# MCU.net
KiCad netlist of a schematic drawn in Altium Designer
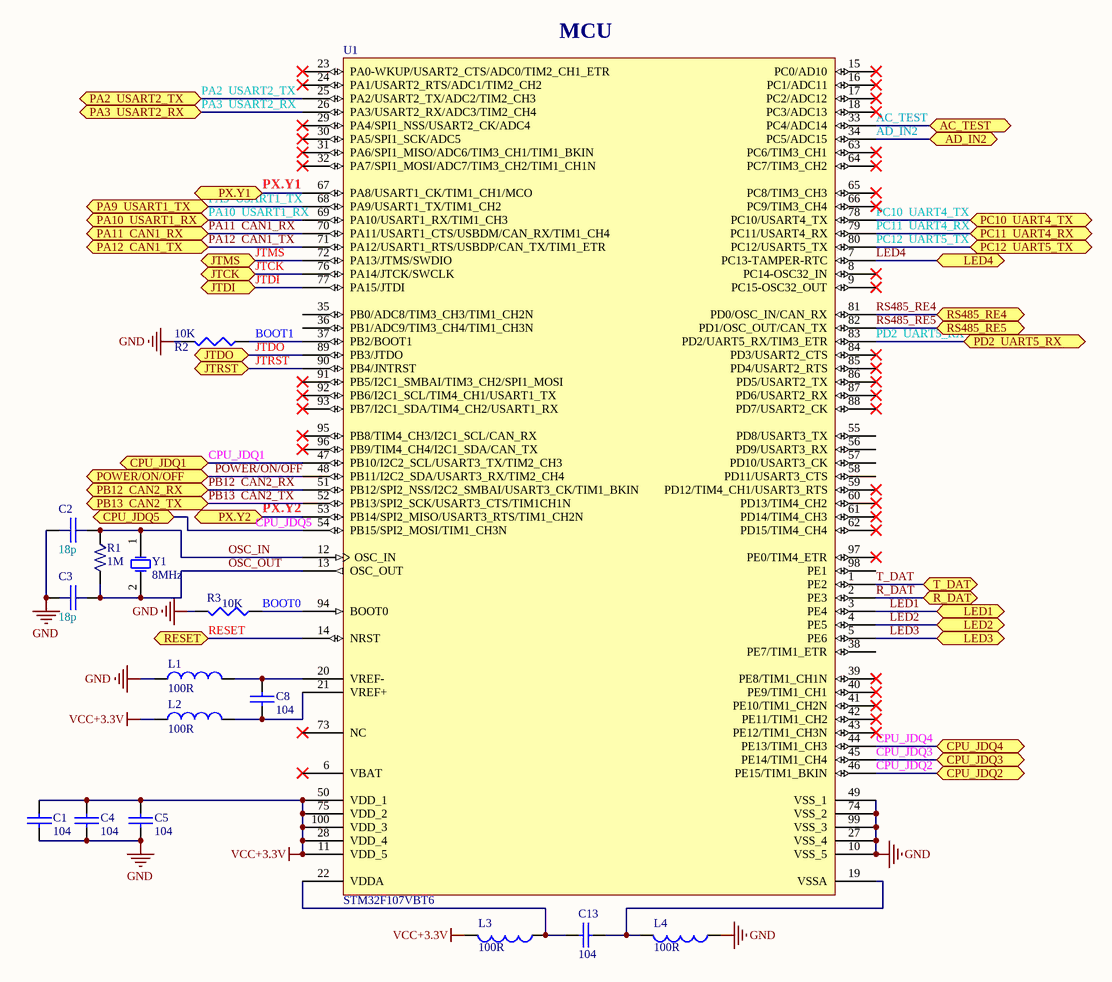
[diagram p0: MCU.SchDoc]

(export (version "E")
  (design (tool "Eeschema 10.0.6"))
  (components
    (comp (ref "C1") (value "104") (footprint "0603") (libsource (lib "INSPUR_SCH") (part "CAP")))
    (comp (ref "C2")
      (value "18p")
      (footprint "0603")
      (description "陶瓷电容")
      (libsource (lib "8CF_V6") (part "CAP"))
    )
    (comp (ref "C3")
      (value "18p")
      (footprint "0603")
      (description "陶瓷电容")
      (libsource (lib "8CF_V6") (part "CAP"))
    )
    (comp (ref "C4") (value "104") (footprint "0603") (libsource (lib "INSPUR_SCH") (part "CAP")))
    (comp (ref "C5") (value "104") (footprint "0603") (libsource (lib "INSPUR_SCH") (part "CAP")))
    (comp (ref "C8") (value "104") (footprint "0603") (libsource (lib "INSPUR_SCH") (part "CAP")))
    (comp (ref "C13") (value "104") (footprint "0603") (libsource (lib "INSPUR_SCH") (part "CAP")))
    (comp (ref "L1") (value "100R") (footprint "0805") (libsource (lib "INSPUR_SCH") (part "INDUCTOR")))
    (comp (ref "L2") (value "100R") (footprint "0805") (libsource (lib "INSPUR_SCH") (part "INDUCTOR")))
    (comp (ref "L3") (value "100R") (footprint "0805") (libsource (lib "INSPUR_SCH") (part "INDUCTOR")))
    (comp (ref "L4") (value "100R") (footprint "0805") (libsource (lib "INSPUR_SCH") (part "INDUCTOR")))
    (comp (ref "R1")
      (value "1M")
      (footprint "0805")
      (description "高精度电阻")
      (libsource (lib "8CF_V6") (part "RES-1%"))
    )
    (comp (ref "R2") (value "10K") (footprint "0603") (libsource (lib "INSPUR_SCH") (part "RES1")))
    (comp (ref "R3") (value "10K") (footprint "0603") (libsource (lib "INSPUR_SCH") (part "RES1")))
    (comp (ref "U1")
      (value "STM32F107VBT6")
      (footprint "LQFP100_L")
      (libsource (lib "mylib") (part "STM32F107VBT6"))
    )
    (comp (ref "Y1")
      (value "8MHz")
      (footprint "XTAL_US")
      (description "Crystal Oscillator")
      (fields (field (name "PUBLISHER") "Altium Limited"))
      (libsource (lib "mylib") (part "XTAL"))
    )
  )
  (nets
    (net (code "1") (name "/AC_TEST") (class "Default")
      (node (ref "U1") (pin "33") (pinfunction "PC4/ADC14_33") (pintype "bidirectional"))
    )
    (net (code "2") (name "/AD_IN2") (class "Default")
      (node (ref "U1") (pin "34") (pinfunction "PC5/ADC15_34") (pintype "bidirectional"))
    )
    (net (code "3") (name "/BOOT0") (class "Default")
      (node (ref "R3") (pin "1") (pinfunction "1_1") (pintype "passive"))
      (node (ref "U1") (pin "94") (pinfunction "BOOT0_94") (pintype "input"))
    )
    (net (code "4") (name "/BOOT1") (class "Default")
      (node (ref "R2") (pin "1") (pinfunction "1_1") (pintype "passive"))
      (node (ref "U1") (pin "37") (pinfunction "PB2/BOOT1_37") (pintype "bidirectional"))
    )
    (net (code "5") (name "/CPU_JDQ1") (class "Default")
      (node (ref "U1") (pin "47") (pinfunction "PB10/I2C2_SCL/USART3_TX/TIM2_CH3_47") (pintype "bidirectional"))
    )
    (net (code "6") (name "/CPU_JDQ2") (class "Default")
      (node (ref "U1") (pin "46") (pinfunction "PE15/TIM1_BKIN_46") (pintype "bidirectional"))
    )
    (net (code "7") (name "/CPU_JDQ3") (class "Default")
      (node (ref "U1") (pin "45") (pinfunction "PE14/TIM1_CH4_45") (pintype "bidirectional"))
    )
    (net (code "8") (name "/CPU_JDQ4") (class "Default")
      (node (ref "U1") (pin "44") (pinfunction "PE13/TIM1_CH3_44") (pintype "bidirectional"))
    )
    (net (code "9") (name "/CPU_JDQ5") (class "Default")
      (node (ref "U1") (pin "54") (pinfunction "PB15/SPI2_MOSI/TIM1_CH3N_54") (pintype "bidirectional"))
    )
    (net (code "10") (name "/JTCK") (class "Default")
      (node (ref "U1") (pin "76") (pinfunction "PA14/JTCK/SWCLK_76") (pintype "bidirectional"))
    )
    (net (code "11") (name "/JTDI") (class "Default")
      (node (ref "U1") (pin "77") (pinfunction "PA15/JTDI_77") (pintype "bidirectional"))
    )
    (net (code "12") (name "/JTDO") (class "Default")
      (node (ref "U1") (pin "89") (pinfunction "PB3/JTDO_89") (pintype "bidirectional"))
    )
    (net (code "13") (name "/JTMS") (class "Default")
      (node (ref "U1") (pin "72") (pinfunction "PA13/JTMS/SWDIO_72") (pintype "bidirectional"))
    )
    (net (code "14") (name "/JTRST") (class "Default")
      (node (ref "U1") (pin "90") (pinfunction "PB4/JNTRST_90") (pintype "bidirectional"))
    )
    (net (code "15") (name "/LED1") (class "Default")
      (node (ref "U1") (pin "3") (pinfunction "PE4_3") (pintype "bidirectional"))
    )
    (net (code "16") (name "/LED2") (class "Default")
      (node (ref "U1") (pin "4") (pinfunction "PE5_4") (pintype "bidirectional"))
    )
    (net (code "17") (name "/LED3") (class "Default")
      (node (ref "U1") (pin "5") (pinfunction "PE6_5") (pintype "bidirectional"))
    )
    (net (code "18") (name "/LED4") (class "Default")
      (node (ref "U1") (pin "7") (pinfunction "PC13-TAMPER-RTC_7") (pintype "bidirectional"))
    )
    (net (code "19") (name "/OSC_IN") (class "Default")
      (node (ref "C2") (pin "1") (pintype "passive"))
      (node (ref "R1") (pin "1") (pintype "passive"))
      (node (ref "U1") (pin "12") (pinfunction "OSC_IN_12") (pintype "input"))
      (node (ref "Y1") (pin "1") (pinfunction "OSC1_1") (pintype "passive"))
    )
    (net (code "20") (name "/OSC_OUT") (class "Default")
      (node (ref "C3") (pin "1") (pintype "passive"))
      (node (ref "R1") (pin "2") (pintype "passive"))
      (node (ref "U1") (pin "13") (pinfunction "OSC_OUT_13") (pintype "output"))
      (node (ref "Y1") (pin "2") (pinfunction "OSC2_2") (pintype "passive"))
    )
    (net (code "21") (name "/PA2  USART2_TX") (class "Default")
      (node (ref "U1") (pin "25") (pinfunction "PA2/USART2_TX/ADC2/TIM2_CH3_25") (pintype "bidirectional"))
    )
    (net (code "22") (name "/PA3  USART2_RX") (class "Default")
      (node (ref "U1") (pin "26") (pinfunction "PA3/USART2_RX/ADC3/TIM2_CH4_26") (pintype "bidirectional"))
    )
    (net (code "23") (name "/PA9  USART1_TX") (class "Default")
      (node (ref "U1") (pin "68") (pinfunction "PA9/USART1_TX/TIM1_CH2_68") (pintype "bidirectional"))
    )
    (net (code "24") (name "/PA10  USART1_RX") (class "Default")
      (node (ref "U1") (pin "69") (pinfunction "PA10/USART1_RX/TIM1_CH3_69") (pintype "bidirectional"))
    )
    (net (code "25") (name "/PA11  CAN1_RX") (class "Default")
      (node (ref "U1") (pin "70") (pinfunction "PA11/USART1_CTS/USBDM/CAN_RX/TIM1_CH4_70") (pintype "bidirectional"))
    )
    (net (code "26") (name "/PA12  CAN1_TX") (class "Default")
      (node (ref "U1") (pin "71") (pinfunction "PA12/USART1_RTS/USBDP/CAN_TX/TIM1_ETR_71") (pintype "bidirectional"))
    )
    (net (code "27") (name "/PB12  CAN2_RX") (class "Default")
      (node (ref "U1") (pin "51") (pinfunction "PB12/SPI2_NSS/I2C2_SMBAI/USART3_CK/TIM1_BKIN_51") (pintype "bidirectional"))
    )
    (net (code "28") (name "/PB13  CAN2_TX") (class "Default")
      (node (ref "U1") (pin "52") (pinfunction "PB13/SPI2_SCK/USART3_CTS/TIM1CH1N_52") (pintype "bidirectional"))
    )
    (net (code "29") (name "/PC10  UART4_TX") (class "Default")
      (node (ref "U1") (pin "78") (pinfunction "PC10/USART4_TX_78") (pintype "bidirectional"))
    )
    (net (code "30") (name "/PC11  UART4_RX") (class "Default")
      (node (ref "U1") (pin "79") (pinfunction "PC11/USART4_RX_79") (pintype "bidirectional"))
    )
    (net (code "31") (name "/PC12  UART5_TX") (class "Default")
      (node (ref "U1") (pin "80") (pinfunction "PC12/USART5_TX_80") (pintype "bidirectional"))
    )
    (net (code "32") (name "/PD2  UART5_RX") (class "Default")
      (node (ref "U1") (pin "83") (pinfunction "PD2/UART5_RX/TIM3_ETR_83") (pintype "bidirectional"))
    )
    (net (code "33") (name "/POWER{slash}ON{slash}OFF") (class "Default")
      (node (ref "U1") (pin "48") (pinfunction "PB11/I2C2_SDA/USART3_RX/TIM2_CH4_48") (pintype "bidirectional"))
    )
    (net (code "34") (name "/PX.Y1") (class "Default")
      (node (ref "U1") (pin "67") (pinfunction "PA8/USART1_CK/TIM1_CH1/MCO_67") (pintype "bidirectional"))
    )
    (net (code "35") (name "/PX.Y2") (class "Default")
      (node (ref "U1") (pin "53") (pinfunction "PB14/SPI2_MISO/USART3_RTS/TIM1_CH2N_53") (pintype "bidirectional"))
    )
    (net (code "36") (name "/RESET") (class "Default")
      (node (ref "U1") (pin "14") (pinfunction "NRST_14") (pintype "bidirectional"))
    )
    (net (code "37") (name "/RS485_RE4") (class "Default")
      (node (ref "U1") (pin "81") (pinfunction "PD0/OSC_IN/CAN_RX_81") (pintype "bidirectional"))
    )
    (net (code "38") (name "/RS485_RE5") (class "Default")
      (node (ref "U1") (pin "82") (pinfunction "PD1/OSC_OUT/CAN_TX_82") (pintype "bidirectional"))
    )
    (net (code "39") (name "/R_DAT") (class "Default")
      (node (ref "U1") (pin "2") (pinfunction "PE3_2") (pintype "bidirectional"))
    )
    (net (code "40") (name "/T_DAT") (class "Default")
      (node (ref "U1") (pin "1") (pinfunction "PE2_1") (pintype "bidirectional"))
    )
    (net (code "41") (name "GND") (class "Default")
      (node (ref "C1") (pin "2") (pinfunction "2_2") (pintype "passive"))
      (node (ref "C2") (pin "2") (pintype "passive"))
      (node (ref "C3") (pin "2") (pintype "passive"))
      (node (ref "C4") (pin "2") (pinfunction "2_2") (pintype "passive"))
      (node (ref "C5") (pin "2") (pinfunction "2_2") (pintype "passive"))
      (node (ref "L1") (pin "1") (pinfunction "1_1") (pintype "passive"))
      (node (ref "L4") (pin "1") (pinfunction "1_1") (pintype "passive"))
      (node (ref "R2") (pin "2") (pinfunction "2_2") (pintype "passive"))
      (node (ref "R3") (pin "2") (pinfunction "2_2") (pintype "passive"))
      (node (ref "U1") (pin "10") (pinfunction "VSS_5_10") (pintype "power_in"))
      (node (ref "U1") (pin "27") (pinfunction "VSS_4_27") (pintype "power_in"))
      (node (ref "U1") (pin "49") (pinfunction "VSS_1_49") (pintype "power_in"))
      (node (ref "U1") (pin "74") (pinfunction "VSS_2_74") (pintype "power_in"))
      (node (ref "U1") (pin "99") (pinfunction "VSS_3_99") (pintype "power_in"))
    )
    (net (code "42") (name "Net-(U1-VDDA)") (class "Default")
      (node (ref "C13") (pin "1") (pinfunction "1_1") (pintype "passive"))
      (node (ref "L3") (pin "1") (pinfunction "1_1") (pintype "passive"))
      (node (ref "U1") (pin "22") (pinfunction "VDDA_22") (pintype "power_in"))
    )
    (net (code "43") (name "Net-(U1-VREF+)") (class "Default")
      (node (ref "C8") (pin "2") (pinfunction "2_2") (pintype "passive"))
      (node (ref "L2") (pin "2") (pinfunction "2_2") (pintype "passive"))
      (node (ref "U1") (pin "21") (pinfunction "VREF+_21") (pintype "power_in"))
    )
    (net (code "44") (name "Net-(U1-VREF-)") (class "Default")
      (node (ref "C8") (pin "1") (pinfunction "1_1") (pintype "passive"))
      (node (ref "L1") (pin "2") (pinfunction "2_2") (pintype "passive"))
      (node (ref "U1") (pin "20") (pinfunction "VREF-_20") (pintype "power_in"))
    )
    (net (code "45") (name "Net-(U1-VSSA)") (class "Default")
      (node (ref "C13") (pin "2") (pinfunction "2_2") (pintype "passive"))
      (node (ref "L4") (pin "2") (pinfunction "2_2") (pintype "passive"))
      (node (ref "U1") (pin "19") (pinfunction "VSSA_19") (pintype "power_in"))
    )
    (net (code "46") (name "VCC+3.3V") (class "Default")
      (node (ref "C1") (pin "1") (pinfunction "1_1") (pintype "passive"))
      (node (ref "C4") (pin "1") (pinfunction "1_1") (pintype "passive"))
      (node (ref "C5") (pin "1") (pinfunction "1_1") (pintype "passive"))
      (node (ref "L2") (pin "1") (pinfunction "1_1") (pintype "passive"))
      (node (ref "L3") (pin "2") (pinfunction "2_2") (pintype "passive"))
      (node (ref "U1") (pin "100") (pinfunction "VDD_3_100") (pintype "power_in"))
      (node (ref "U1") (pin "11") (pinfunction "VDD_5_11") (pintype "power_in"))
      (node (ref "U1") (pin "28") (pinfunction "VDD_4_28") (pintype "power_in"))
      (node (ref "U1") (pin "50") (pinfunction "VDD_1_50") (pintype "power_in"))
      (node (ref "U1") (pin "75") (pinfunction "VDD_2_75") (pintype "power_in"))
    )
    (net (code "47") (name "unconnected-(U1-NC-Pad73)") (class "Default")
      (node (ref "U1") (pin "73") (pinfunction "NC_73") (pintype "passive+no_connect"))
    )
    (net (code "48") (name "unconnected-(U1-PA0-WKUP{slash}USART2_CTS{slash}ADC0{slash}TIM2_CH1_ETR-Pad23)") (class "Default")
      (node (ref "U1") (pin "23") (pinfunction "PA0-WKUP/USART2_CTS/ADC0/TIM2_CH1_ETR_23") (pintype "bidirectional+no_connect"))
    )
    (net (code "49") (name "unconnected-(U1-PA1{slash}USART2_RTS{slash}ADC1{slash}TIM2_CH2-Pad24)") (class "Default")
      (node (ref "U1") (pin "24") (pinfunction "PA1/USART2_RTS/ADC1/TIM2_CH2_24") (pintype "bidirectional+no_connect"))
    )
    (net (code "50") (name "unconnected-(U1-PA4{slash}SPI1_NSS{slash}USART2_CK{slash}ADC4-Pad29)") (class "Default")
      (node (ref "U1") (pin "29") (pinfunction "PA4/SPI1_NSS/USART2_CK/ADC4_29") (pintype "bidirectional+no_connect"))
    )
    (net (code "51") (name "unconnected-(U1-PA5{slash}SPI1_SCK{slash}ADC5-Pad30)") (class "Default")
      (node (ref "U1") (pin "30") (pinfunction "PA5/SPI1_SCK/ADC5_30") (pintype "bidirectional+no_connect"))
    )
    (net (code "52") (name "unconnected-(U1-PA6{slash}SPI1_MISO{slash}ADC6{slash}TIM3_CH1{slash}TIM1_BKIN-Pad31)") (class "Default")
      (node (ref "U1") (pin "31") (pinfunction "PA6/SPI1_MISO/ADC6/TIM3_CH1/TIM1_BKIN_31") (pintype "bidirectional+no_connect"))
    )
    (net (code "53") (name "unconnected-(U1-PA7{slash}SPI1_MOSI{slash}ADC7{slash}TIM3_CH2{slash}TIM1_CH1N-Pad32)") (class "Default")
      (node (ref "U1") (pin "32") (pinfunction "PA7/SPI1_MOSI/ADC7/TIM3_CH2/TIM1_CH1N_32") (pintype "bidirectional+no_connect"))
    )
    (net (code "54") (name "unconnected-(U1-PB0{slash}ADC8{slash}TIM3_CH3{slash}TIM1_CH2N-Pad35)") (class "Default")
      (node (ref "U1") (pin "35") (pinfunction "PB0/ADC8/TIM3_CH3/TIM1_CH2N_35") (pintype "bidirectional"))
    )
    (net (code "55") (name "unconnected-(U1-PB1{slash}ADC9{slash}TIM3_CH4{slash}TIM1_CH3N-Pad36)") (class "Default")
      (node (ref "U1") (pin "36") (pinfunction "PB1/ADC9/TIM3_CH4/TIM1_CH3N_36") (pintype "bidirectional"))
    )
    (net (code "56") (name "unconnected-(U1-PB5{slash}I2C1_SMBAI{slash}TIM3_CH2{slash}SPI1_MOSI-Pad91)") (class "Default")
      (node (ref "U1") (pin "91") (pinfunction "PB5/I2C1_SMBAI/TIM3_CH2/SPI1_MOSI_91") (pintype "bidirectional+no_connect"))
    )
    (net (code "57") (name "unconnected-(U1-PB6{slash}I2C1_SCL{slash}TIM4_CH1{slash}USART1_TX-Pad92)") (class "Default")
      (node (ref "U1") (pin "92") (pinfunction "PB6/I2C1_SCL/TIM4_CH1/USART1_TX_92") (pintype "bidirectional+no_connect"))
    )
    (net (code "58") (name "unconnected-(U1-PB7{slash}I2C1_SDA{slash}TIM4_CH2{slash}USART1_RX-Pad93)") (class "Default")
      (node (ref "U1") (pin "93") (pinfunction "PB7/I2C1_SDA/TIM4_CH2/USART1_RX_93") (pintype "bidirectional+no_connect"))
    )
    (net (code "59") (name "unconnected-(U1-PB8{slash}TIM4_CH3{slash}I2C1_SCL{slash}CAN_RX-Pad95)") (class "Default")
      (node (ref "U1") (pin "95") (pinfunction "PB8/TIM4_CH3/I2C1_SCL/CAN_RX_95") (pintype "bidirectional+no_connect"))
    )
    (net (code "60") (name "unconnected-(U1-PB9{slash}TIM4_CH4{slash}I2C1_SDA{slash}CAN_TX-Pad96)") (class "Default")
      (node (ref "U1") (pin "96") (pinfunction "PB9/TIM4_CH4/I2C1_SDA/CAN_TX_96") (pintype "bidirectional+no_connect"))
    )
    (net (code "61") (name "unconnected-(U1-PC0{slash}AD10-Pad15)") (class "Default")
      (node (ref "U1") (pin "15") (pinfunction "PC0/AD10_15") (pintype "bidirectional+no_connect"))
    )
    (net (code "62") (name "unconnected-(U1-PC1{slash}ADC11-Pad16)") (class "Default")
      (node (ref "U1") (pin "16") (pinfunction "PC1/ADC11_16") (pintype "bidirectional+no_connect"))
    )
    (net (code "63") (name "unconnected-(U1-PC2{slash}ADC12-Pad17)") (class "Default")
      (node (ref "U1") (pin "17") (pinfunction "PC2/ADC12_17") (pintype "bidirectional+no_connect"))
    )
    (net (code "64") (name "unconnected-(U1-PC3{slash}ADC13-Pad18)") (class "Default")
      (node (ref "U1") (pin "18") (pinfunction "PC3/ADC13_18") (pintype "bidirectional+no_connect"))
    )
    (net (code "65") (name "unconnected-(U1-PC6{slash}TIM3_CH1-Pad63)") (class "Default")
      (node (ref "U1") (pin "63") (pinfunction "PC6/TIM3_CH1_63") (pintype "bidirectional+no_connect"))
    )
    (net (code "66") (name "unconnected-(U1-PC7{slash}TIM3_CH2-Pad64)") (class "Default")
      (node (ref "U1") (pin "64") (pinfunction "PC7/TIM3_CH2_64") (pintype "bidirectional+no_connect"))
    )
    (net (code "67") (name "unconnected-(U1-PC8{slash}TIM3_CH3-Pad65)") (class "Default")
      (node (ref "U1") (pin "65") (pinfunction "PC8/TIM3_CH3_65") (pintype "bidirectional+no_connect"))
    )
    (net (code "68") (name "unconnected-(U1-PC9{slash}TIM3_CH4-Pad66)") (class "Default")
      (node (ref "U1") (pin "66") (pinfunction "PC9/TIM3_CH4_66") (pintype "bidirectional+no_connect"))
    )
    (net (code "69") (name "unconnected-(U1-PC14-OSC32_IN-Pad8)") (class "Default")
      (node (ref "U1") (pin "8") (pinfunction "PC14-OSC32_IN_8") (pintype "bidirectional+no_connect"))
    )
    (net (code "70") (name "unconnected-(U1-PC15-OSC32_OUT-Pad9)") (class "Default")
      (node (ref "U1") (pin "9") (pinfunction "PC15-OSC32_OUT_9") (pintype "bidirectional+no_connect"))
    )
    (net (code "71") (name "unconnected-(U1-PD3{slash}USART2_CTS-Pad84)") (class "Default")
      (node (ref "U1") (pin "84") (pinfunction "PD3/USART2_CTS_84") (pintype "bidirectional+no_connect"))
    )
    (net (code "72") (name "unconnected-(U1-PD4{slash}USART2_RTS-Pad85)") (class "Default")
      (node (ref "U1") (pin "85") (pinfunction "PD4/USART2_RTS_85") (pintype "bidirectional+no_connect"))
    )
    (net (code "73") (name "unconnected-(U1-PD5{slash}USART2_TX-Pad86)") (class "Default")
      (node (ref "U1") (pin "86") (pinfunction "PD5/USART2_TX_86") (pintype "bidirectional+no_connect"))
    )
    (net (code "74") (name "unconnected-(U1-PD6{slash}USART2_RX-Pad87)") (class "Default")
      (node (ref "U1") (pin "87") (pinfunction "PD6/USART2_RX_87") (pintype "bidirectional+no_connect"))
    )
    (net (code "75") (name "unconnected-(U1-PD7{slash}USART2_CK-Pad88)") (class "Default")
      (node (ref "U1") (pin "88") (pinfunction "PD7/USART2_CK_88") (pintype "bidirectional+no_connect"))
    )
    (net (code "76") (name "unconnected-(U1-PD8{slash}USART3_TX-Pad55)") (class "Default")
      (node (ref "U1") (pin "55") (pinfunction "PD8/USART3_TX_55") (pintype "bidirectional"))
    )
    (net (code "77") (name "unconnected-(U1-PD9{slash}USART3_RX-Pad56)") (class "Default")
      (node (ref "U1") (pin "56") (pinfunction "PD9/USART3_RX_56") (pintype "bidirectional"))
    )
    (net (code "78") (name "unconnected-(U1-PD10{slash}USART3_CK-Pad57)") (class "Default")
      (node (ref "U1") (pin "57") (pinfunction "PD10/USART3_CK_57") (pintype "bidirectional"))
    )
    (net (code "79") (name "unconnected-(U1-PD11{slash}USART3_CTS-Pad58)") (class "Default")
      (node (ref "U1") (pin "58") (pinfunction "PD11/USART3_CTS_58") (pintype "bidirectional"))
    )
    (net (code "80") (name "unconnected-(U1-PD12{slash}TIM4_CH1{slash}USART3_RTS-Pad59)") (class "Default")
      (node (ref "U1") (pin "59") (pinfunction "PD12/TIM4_CH1/USART3_RTS_59") (pintype "bidirectional+no_connect"))
    )
    (net (code "81") (name "unconnected-(U1-PD13{slash}TIM4_CH2-Pad60)") (class "Default")
      (node (ref "U1") (pin "60") (pinfunction "PD13/TIM4_CH2_60") (pintype "bidirectional+no_connect"))
    )
    (net (code "82") (name "unconnected-(U1-PD14{slash}TIM4_CH3-Pad61)") (class "Default")
      (node (ref "U1") (pin "61") (pinfunction "PD14/TIM4_CH3_61") (pintype "bidirectional+no_connect"))
    )
    (net (code "83") (name "unconnected-(U1-PD15{slash}TIM4_CH4-Pad62)") (class "Default")
      (node (ref "U1") (pin "62") (pinfunction "PD15/TIM4_CH4_62") (pintype "bidirectional+no_connect"))
    )
    (net (code "84") (name "unconnected-(U1-PE0{slash}TIM4_ETR-Pad97)") (class "Default")
      (node (ref "U1") (pin "97") (pinfunction "PE0/TIM4_ETR_97") (pintype "bidirectional+no_connect"))
    )
    (net (code "85") (name "unconnected-(U1-PE1-Pad98)") (class "Default")
      (node (ref "U1") (pin "98") (pinfunction "PE1_98") (pintype "bidirectional"))
    )
    (net (code "86") (name "unconnected-(U1-PE7{slash}TIM1_ETR-Pad38)") (class "Default")
      (node (ref "U1") (pin "38") (pinfunction "PE7/TIM1_ETR_38") (pintype "bidirectional"))
    )
    (net (code "87") (name "unconnected-(U1-PE8{slash}TIM1_CH1N-Pad39)") (class "Default")
      (node (ref "U1") (pin "39") (pinfunction "PE8/TIM1_CH1N_39") (pintype "bidirectional+no_connect"))
    )
    (net (code "88") (name "unconnected-(U1-PE9{slash}TIM1_CH1-Pad40)") (class "Default")
      (node (ref "U1") (pin "40") (pinfunction "PE9/TIM1_CH1_40") (pintype "bidirectional+no_connect"))
    )
    (net (code "89") (name "unconnected-(U1-PE10{slash}TIM1_CH2N-Pad41)") (class "Default")
      (node (ref "U1") (pin "41") (pinfunction "PE10/TIM1_CH2N_41") (pintype "bidirectional+no_connect"))
    )
    (net (code "90") (name "unconnected-(U1-PE11{slash}TIM1_CH2-Pad42)") (class "Default")
      (node (ref "U1") (pin "42") (pinfunction "PE11/TIM1_CH2_42") (pintype "bidirectional+no_connect"))
    )
    (net (code "91") (name "unconnected-(U1-PE12{slash}TIM1_CH3N-Pad43)") (class "Default")
      (node (ref "U1") (pin "43") (pinfunction "PE12/TIM1_CH3N_43") (pintype "bidirectional+no_connect"))
    )
    (net (code "92") (name "unconnected-(U1-VBAT-Pad6)") (class "Default")
      (node (ref "U1") (pin "6") (pinfunction "VBAT_6") (pintype "power_in+no_connect"))
    )
  )
)
